# Illuminator_BOOST_Extended.net
KiCad netlist of a schematic drawn in EAGLE
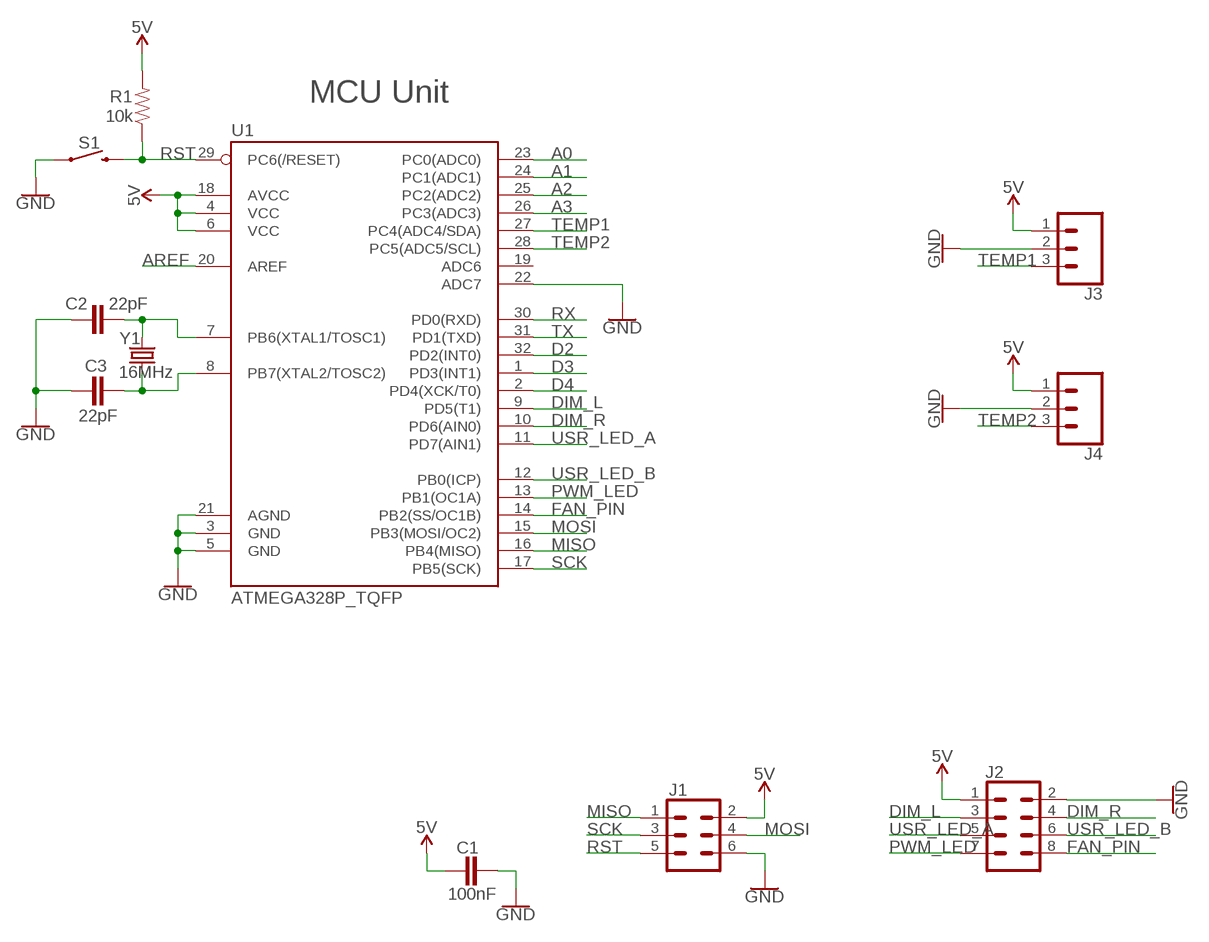
[diagram p0: schematic, sheet 1]

(export (version "E")
  (design (tool "Eeschema 10.0.6"))
  (components
    (comp (ref "C1")
      (value "100nF")
      (footprint "eagle-import:0805")
      (libsource (lib "eagle-import") (part "1.0UF-0805-25V-(+80/-20%)"))
    )
    (comp (ref "C2")
      (value "22pF")
      (footprint "eagle-import:0603")
      (libsource (lib "eagle-import") (part "22PF-0603-50V-5%"))
    )
    (comp (ref "C3")
      (value "22pF")
      (footprint "eagle-import:0603")
      (libsource (lib "eagle-import") (part "22PF-0603-50V-5%"))
    )
    (comp (ref "J1")
      (value "CONN_03X2NO_SILK")
      (footprint "eagle-import:2X3-NS")
      (libsource (lib "eagle-import") (part "CONN_03X2NO_SILK"))
    )
    (comp (ref "J2")
      (value "CONN_04X2")
      (footprint "eagle-import:2X4")
      (libsource (lib "eagle-import") (part "CONN_04X2"))
    )
    (comp (ref "J3")
      (value "CONN_03JST-PTH-VERT")
      (footprint "eagle-import:JST-3-PTH-VERT")
      (libsource (lib "eagle-import") (part "CONN_03JST-PTH-VERT"))
    )
    (comp (ref "J4")
      (value "CONN_03JST-PTH-VERT")
      (footprint "eagle-import:JST-3-PTH-VERT")
      (libsource (lib "eagle-import") (part "CONN_03JST-PTH-VERT"))
    )
    (comp (ref "R1")
      (value "10k")
      (footprint "eagle-import:1206")
      (libsource (lib "eagle-import") (part "RESISTOR1206"))
    )
    (comp (ref "S1")
      (value "MOMENTARY-SWITCH-SPST-SMD-6.0X3.5MM")
      (footprint "eagle-import:TACTILE_SWITCH_SMD_6.0X3.5MM")
      (libsource (lib "eagle-import") (part "MOMENTARY-SWITCH-SPST-SMD-6.0X3.5MM"))
    )
    (comp (ref "U1")
      (value "ATMEGA328P_TQFP")
      (footprint "eagle-import:TQFP32-08")
      (libsource (lib "eagle-import") (part "ATMEGA328P_TQFP"))
    )
    (comp (ref "Y1")
      (value "16MHz")
      (footprint "eagle-import:CRYSTAL-SMD-5X3.2-4PAD")
      (libsource (lib "eagle-import") (part "CRYSTAL-16MHZSMD-5X3.2"))
    )
  )
  (nets
    (net (code "1") (name "/A0") (class "Default")
      (node (ref "U1") (pin "23") (pinfunction "PC0(ADC0)_23") (pintype "bidirectional"))
    )
    (net (code "2") (name "/A1") (class "Default")
      (node (ref "U1") (pin "24") (pinfunction "PC1(ADC1)_24") (pintype "bidirectional"))
    )
    (net (code "3") (name "/A2") (class "Default")
      (node (ref "U1") (pin "25") (pinfunction "PC2(ADC2)_25") (pintype "bidirectional"))
    )
    (net (code "4") (name "/A3") (class "Default")
      (node (ref "U1") (pin "26") (pinfunction "PC3(ADC3)_26") (pintype "bidirectional"))
    )
    (net (code "5") (name "/AREF") (class "Default")
      (node (ref "U1") (pin "20") (pinfunction "AREF_20") (pintype "bidirectional"))
    )
    (net (code "6") (name "/D2") (class "Default")
      (node (ref "U1") (pin "32") (pinfunction "PD2(INT0)_32") (pintype "bidirectional"))
    )
    (net (code "7") (name "/D3") (class "Default")
      (node (ref "U1") (pin "1") (pinfunction "PD3(INT1)_1") (pintype "bidirectional"))
    )
    (net (code "8") (name "/D4") (class "Default")
      (node (ref "U1") (pin "2") (pinfunction "PD4(XCK/T0)_2") (pintype "bidirectional"))
    )
    (net (code "9") (name "/DIM_L") (class "Default")
      (node (ref "J2") (pin "3") (pinfunction "3_3") (pintype "passive"))
      (node (ref "U1") (pin "9") (pinfunction "PD5(T1)_9") (pintype "bidirectional"))
    )
    (net (code "10") (name "/DIM_R") (class "Default")
      (node (ref "J2") (pin "4") (pinfunction "4_4") (pintype "passive"))
      (node (ref "U1") (pin "10") (pinfunction "PD6(AIN0)_10") (pintype "bidirectional"))
    )
    (net (code "11") (name "/FAN_PIN") (class "Default")
      (node (ref "J2") (pin "8") (pinfunction "8_8") (pintype "passive"))
      (node (ref "U1") (pin "14") (pinfunction "PB2(SS/OC1B)_14") (pintype "bidirectional"))
    )
    (net (code "12") (name "/MISO") (class "Default")
      (node (ref "J1") (pin "1") (pinfunction "1_1") (pintype "bidirectional"))
      (node (ref "U1") (pin "16") (pinfunction "PB4(MISO)_16") (pintype "bidirectional"))
    )
    (net (code "13") (name "/MOSI") (class "Default")
      (node (ref "J1") (pin "4") (pinfunction "4_4") (pintype "bidirectional"))
      (node (ref "U1") (pin "15") (pinfunction "PB3(MOSI/OC2)_15") (pintype "bidirectional"))
    )
    (net (code "14") (name "/PWM_LED") (class "Default")
      (node (ref "J2") (pin "7") (pinfunction "7_7") (pintype "passive"))
      (node (ref "U1") (pin "13") (pinfunction "PB1(OC1A)_13") (pintype "bidirectional"))
    )
    (net (code "15") (name "/RST") (class "Default")
      (node (ref "J1") (pin "5") (pinfunction "5_5") (pintype "bidirectional"))
      (node (ref "R1") (pin "1") (pinfunction "1_1") (pintype "passive"))
      (node (ref "S1") (pin "2") (pinfunction "2_2") (pintype "passive"))
      (node (ref "U1") (pin "29") (pinfunction "PC6(/RESET)_29") (pintype "bidirectional"))
    )
    (net (code "16") (name "/RX") (class "Default")
      (node (ref "U1") (pin "30") (pinfunction "PD0(RXD)_30") (pintype "bidirectional"))
    )
    (net (code "17") (name "/SCK") (class "Default")
      (node (ref "J1") (pin "3") (pinfunction "3_3") (pintype "bidirectional"))
      (node (ref "U1") (pin "17") (pinfunction "PB5(SCK)_17") (pintype "bidirectional"))
    )
    (net (code "18") (name "/TEMP1") (class "Default")
      (node (ref "J3") (pin "3") (pinfunction "3_3") (pintype "passive"))
      (node (ref "U1") (pin "27") (pinfunction "PC4(ADC4/SDA)_27") (pintype "bidirectional"))
    )
    (net (code "19") (name "/TEMP2") (class "Default")
      (node (ref "J4") (pin "3") (pinfunction "3_3") (pintype "passive"))
      (node (ref "U1") (pin "28") (pinfunction "PC5(ADC5/SCL)_28") (pintype "bidirectional"))
    )
    (net (code "20") (name "/TX") (class "Default")
      (node (ref "U1") (pin "31") (pinfunction "PD1(TXD)_31") (pintype "bidirectional"))
    )
    (net (code "21") (name "/USR_LED_A") (class "Default")
      (node (ref "J2") (pin "5") (pinfunction "5_5") (pintype "passive"))
      (node (ref "U1") (pin "11") (pinfunction "PD7(AIN1)_11") (pintype "bidirectional"))
    )
    (net (code "22") (name "/USR_LED_B") (class "Default")
      (node (ref "J2") (pin "6") (pinfunction "6_6") (pintype "passive"))
      (node (ref "U1") (pin "12") (pinfunction "PB0(ICP)_12") (pintype "bidirectional"))
    )
    (net (code "23") (name "5V") (class "Default")
      (node (ref "C1") (pin "1") (pinfunction "1_1") (pintype "passive"))
      (node (ref "J1") (pin "2") (pinfunction "2_2") (pintype "bidirectional"))
      (node (ref "J2") (pin "1") (pinfunction "1_1") (pintype "passive"))
      (node (ref "J3") (pin "1") (pinfunction "1_1") (pintype "passive"))
      (node (ref "J4") (pin "1") (pinfunction "1_1") (pintype "passive"))
      (node (ref "R1") (pin "2") (pinfunction "2_2") (pintype "passive"))
      (node (ref "U1") (pin "18") (pinfunction "AVCC_18") (pintype "bidirectional"))
      (node (ref "U1") (pin "4") (pinfunction "VCC_4") (pintype "bidirectional"))
      (node (ref "U1") (pin "6") (pinfunction "VCC_6") (pintype "bidirectional"))
    )
    (net (code "24") (name "GND") (class "Default")
      (node (ref "C1") (pin "2") (pinfunction "2_2") (pintype "passive"))
      (node (ref "C2") (pin "1") (pinfunction "1_1") (pintype "passive"))
      (node (ref "C3") (pin "1") (pinfunction "1_1") (pintype "passive"))
      (node (ref "J1") (pin "6") (pinfunction "6_6") (pintype "bidirectional"))
      (node (ref "J2") (pin "2") (pinfunction "2_2") (pintype "passive"))
      (node (ref "J3") (pin "2") (pinfunction "2_2") (pintype "passive"))
      (node (ref "J4") (pin "2") (pinfunction "2_2") (pintype "passive"))
      (node (ref "S1") (pin "1") (pinfunction "1_1") (pintype "passive"))
      (node (ref "U1") (pin "21") (pinfunction "AGND_21") (pintype "bidirectional"))
      (node (ref "U1") (pin "22") (pinfunction "ADC7_22") (pintype "bidirectional"))
      (node (ref "U1") (pin "3") (pinfunction "GND_3") (pintype "bidirectional"))
      (node (ref "U1") (pin "5") (pinfunction "GND_5") (pintype "bidirectional"))
    )
    (net (code "25") (name "Net-(U1-PB6(XTAL1{slash}TOSC1))") (class "Default")
      (node (ref "C2") (pin "2") (pinfunction "2_2") (pintype "passive"))
      (node (ref "U1") (pin "7") (pinfunction "PB6(XTAL1/TOSC1)_7") (pintype "bidirectional"))
      (node (ref "Y1") (pin "3") (pinfunction "2_3") (pintype "passive"))
    )
    (net (code "26") (name "Net-(U1-PB7(XTAL2{slash}TOSC2))") (class "Default")
      (node (ref "C3") (pin "2") (pinfunction "2_2") (pintype "passive"))
      (node (ref "U1") (pin "8") (pinfunction "PB7(XTAL2/TOSC2)_8") (pintype "bidirectional"))
      (node (ref "Y1") (pin "1") (pinfunction "1_1") (pintype "passive"))
    )
    (net (code "27") (name "unconnected-(U1-ADC6-Pad19)") (class "Default")
      (node (ref "U1") (pin "19") (pinfunction "ADC6_19") (pintype "bidirectional"))
    )
  )
)
